# Interface.net
KiCad netlist of a schematic drawn in Altium Designer
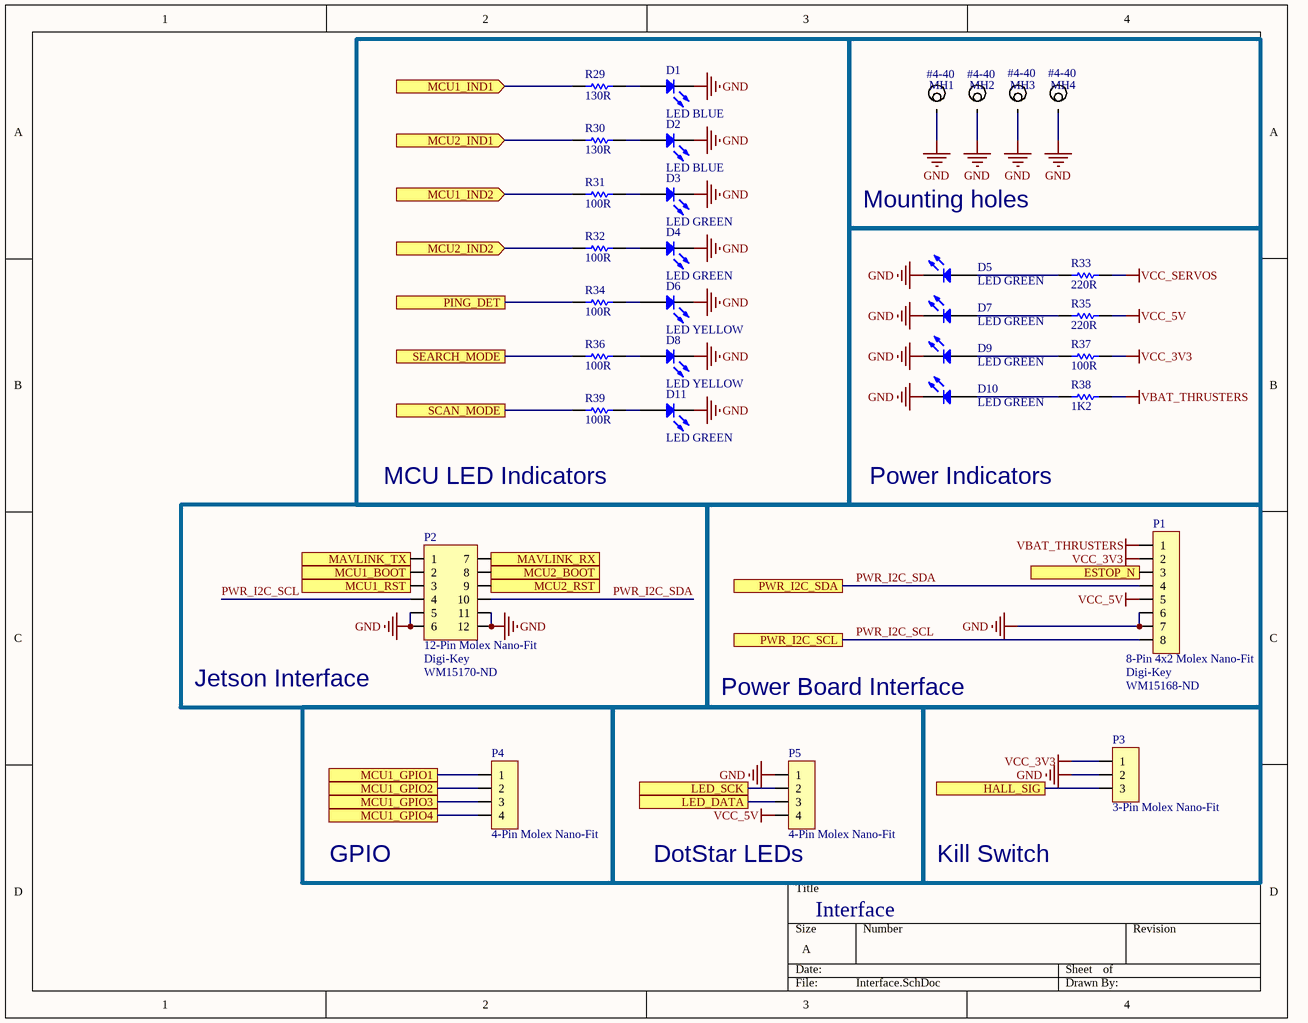
[diagram p0: Interface.SchDoc]

(export (version "E")
  (design (tool "Eeschema 10.0.6"))
  (components
    (comp (ref "D1")
      (value "LED BLUE")
      (footprint "LED_0805")
      (description "led")
      (libsource (lib "CMR_Miscellaneous_Devices") (part "LED0"))
    )
    (comp (ref "D2")
      (value "LED BLUE")
      (footprint "LED_0805")
      (description "led")
      (libsource (lib "CMR_Miscellaneous_Devices") (part "LED0"))
    )
    (comp (ref "D3")
      (value "LED GREEN")
      (footprint "LED_0805")
      (description "led")
      (fields
        (field (name "MANUFACTURER") "Lite-On Inc.")
        (field (name "MANUFACTURER PART NUMBER") "LTST-C171KGKT")
      )
      (libsource (lib "CMR_Miscellaneous_Devices") (part "LED0"))
    )
    (comp (ref "D4")
      (value "LED GREEN")
      (footprint "LED_0805")
      (description "led")
      (fields
        (field (name "MANUFACTURER") "Lite-On Inc.")
        (field (name "MANUFACTURER PART NUMBER") "LTST-C171KGKT")
      )
      (libsource (lib "CMR_Miscellaneous_Devices") (part "LED0"))
    )
    (comp (ref "D5")
      (value "LED GREEN")
      (footprint "LED_0805")
      (description "led")
      (fields
        (field (name "MANUFACTURER") "Lite-On Inc.")
        (field (name "MANUFACTURER PART NUMBER") "LTST-C171KGKT")
      )
      (libsource (lib "CMR_Miscellaneous_Devices") (part "LED0"))
    )
    (comp (ref "D6")
      (value "LED YELLOW")
      (footprint "LED_0805")
      (description "led\r\n LTST-C171KSKT")
      (fields
        (field (name "MANUFACTURER") "Lite-On Inc.")
        (field (name "MANUFACTURER PART NUMBER") "LTST-C171KGKT")
      )
      (libsource (lib "CMR_Miscellaneous_Devices") (part "LED0"))
    )
    (comp (ref "D7")
      (value "LED GREEN")
      (footprint "LED_0805")
      (description "led")
      (fields
        (field (name "MANUFACTURER") "Lite-On Inc.")
        (field (name "MANUFACTURER PART NUMBER") "LTST-C171KGKT")
      )
      (libsource (lib "CMR_Miscellaneous_Devices") (part "LED0"))
    )
    (comp (ref "D8")
      (value "LED YELLOW")
      (footprint "LED_0805")
      (description "led\r\n LTST-C171KSKT")
      (fields
        (field (name "MANUFACTURER") "Lite-On Inc.")
        (field (name "MANUFACTURER PART NUMBER") "LTST-C171KGKT")
      )
      (libsource (lib "CMR_Miscellaneous_Devices") (part "LED0"))
    )
    (comp (ref "D9")
      (value "LED GREEN")
      (footprint "LED_0805")
      (description "led")
      (fields
        (field (name "MANUFACTURER") "Lite-On Inc.")
        (field (name "MANUFACTURER PART NUMBER") "LTST-C171KGKT")
      )
      (libsource (lib "CMR_Miscellaneous_Devices") (part "LED0"))
    )
    (comp (ref "D10")
      (value "LED GREEN")
      (footprint "LED_0805")
      (description "led")
      (fields
        (field (name "MANUFACTURER") "Lite-On Inc.")
        (field (name "MANUFACTURER PART NUMBER") "LTST-C171KGKT")
      )
      (libsource (lib "CMR_Miscellaneous_Devices") (part "LED0"))
    )
    (comp (ref "D11")
      (value "LED GREEN")
      (footprint "LED_0805")
      (description "led")
      (fields
        (field (name "MANUFACTURER") "Lite-On Inc.")
        (field (name "MANUFACTURER PART NUMBER") "LTST-C171KGKT")
      )
      (libsource (lib "CMR_Miscellaneous_Devices") (part "LED0"))
    )
    (comp (ref "MH1")
      (value "#4-40")
      (footprint "Mounting Hole #4-40")
      (description "Mounting Hole for ANSI #4-40 w/ Flat Washer, Loose Fit")
      (libsource (lib "CMR_PCB_Components") (part "Mounting Hole #4-40, Loose Fit"))
    )
    (comp (ref "MH2")
      (value "#4-40")
      (footprint "Mounting Hole #4-40")
      (description "Mounting Hole for ANSI #4-40 w/ Flat Washer, Loose Fit")
      (libsource (lib "CMR_PCB_Components") (part "Mounting Hole #4-40, Loose Fit"))
    )
    (comp (ref "MH3")
      (value "#4-40")
      (footprint "Mounting Hole #4-40")
      (description "Mounting Hole for ANSI #4-40 w/ Flat Washer, Loose Fit")
      (libsource (lib "CMR_PCB_Components") (part "Mounting Hole #4-40, Loose Fit"))
    )
    (comp (ref "MH4")
      (value "#4-40")
      (footprint "Mounting Hole #4-40")
      (description "Mounting Hole for ANSI #4-40 w/ Flat Washer, Loose Fit")
      (libsource (lib "CMR_PCB_Components") (part "Mounting Hole #4-40, Loose Fit"))
    )
    (comp (ref "P1")
      (value "8-Pin 4x2 Molex Nano-Fit")
      (footprint "MOLEX NANO-FIT 2x4")
      (description "NanoFit RA Hdr TH DR 8Ckt")
      (fields
        (field (name "PART NUMBER") "105314-1216")
        (field (name "MANUFACTURER") "Molex")
        (field (name "SUPPLIER 1") "Digi-Key")
        (field (name "SUPPLIER PART NUMBER 1") "WM15168-ND")
      )
      (libsource (lib "CMR_Connectors") (part "8-Pin 2-Row Nano-Fit"))
    )
    (comp (ref "P2")
      (value "12-Pin Molex Nano-Fit")
      (footprint "MOLEX NANO-FIT 2X6 - Right Angle")
      (description "NanoFit RA Hdr TH DR 12Ckt")
      (fields (field (name "SUPPLIER 1") "Digi-Key") (field (name "SUPPLIER PART NUMBER 1") "WM15170-ND"))
      (libsource (lib "CMR_Connectors") (part "12-Pin 2-Row Nano-Fit"))
    )
    (comp (ref "P3")
      (value "3-Pin Molex Nano-Fit")
      (footprint "MOLEX NANO-FIT 1X3")
      (description "NanoFit RA Hdr TH SR 3Ckt")
      (fields (field (name "MANUFACTURER") "Molex") (field (name "PART NUMBER") "105313-1204"))
      (libsource (lib "CMR_Connectors") (part "3-Pin Nano-Fit"))
    )
    (comp (ref "P4")
      (value "4-Pin Molex Nano-Fit")
      (footprint "MOLEX NANO-FIT 1X4")
      (description "NanoFit RA Hdr TH SR 4Ckt")
      (fields (field (name "MANUFACTURER") "Molex") (field (name "PART NUMBER") "105313-1204"))
      (libsource (lib "CMR_Connectors") (part "4-Pin Nano-Fit"))
    )
    (comp (ref "P5")
      (value "4-Pin Molex Nano-Fit")
      (footprint "MOLEX NANO-FIT 1X4")
      (description "NanoFit RA Hdr TH SR 4Ckt")
      (fields (field (name "MANUFACTURER") "Molex") (field (name "PART NUMBER") "105313-1204"))
      (libsource (lib "CMR_Connectors") (part "4-Pin Nano-Fit"))
    )
    (comp (ref "R29")
      (value "130R")
      (footprint "RESC0603(1608)_N")
      (description "130R 0.1W 1% 0603 (1608 Metric)  SMD")
      (fields (field (name "POWER") "0.1 W") (field (name "TOLERANCE") "1 %"))
      (libsource (lib "Altium Content Vault") (part "CMP-1012-00409-1"))
    )
    (comp (ref "R30")
      (value "130R")
      (footprint "RESC0603(1608)_N")
      (description "130R 0.1W 1% 0603 (1608 Metric)  SMD")
      (fields (field (name "POWER") "0.1 W") (field (name "TOLERANCE") "1 %"))
      (libsource (lib "Altium Content Vault") (part "CMP-1012-00409-1"))
    )
    (comp (ref "R31")
      (value "100R")
      (footprint "RESC0603(1608)_N")
      (description "100R 0.1W 5% 0603 (1608 Metric)  SMD")
      (fields (field (name "TOLERANCE") "5 %") (field (name "POWER") "0.1 W"))
      (libsource (lib "Altium Content Vault") (part "CMP-1012-00050-1"))
    )
    (comp (ref "R32")
      (value "100R")
      (footprint "RESC0603(1608)_N")
      (description "100R 0.1W 5% 0603 (1608 Metric)  SMD")
      (fields (field (name "TOLERANCE") "5 %") (field (name "POWER") "0.1 W"))
      (libsource (lib "Altium Content Vault") (part "CMP-1012-00050-1"))
    )
    (comp (ref "R33")
      (value "220R")
      (footprint "RESC0603(1608)_N")
      (description "220R 0.1W 5% 0603 (1608 Metric)  SMD")
      (fields (field (name "POWER") "0.1 W") (field (name "TOLERANCE") "5 %"))
      (libsource (lib "Altium Content Vault") (part "RES"))
    )
    (comp (ref "R34")
      (value "100R")
      (footprint "RESC0603(1608)_N")
      (description "100R 0.1W 5% 0603 (1608 Metric)  SMD")
      (fields (field (name "TOLERANCE") "5 %") (field (name "POWER") "0.1 W"))
      (libsource (lib "Altium Content Vault") (part "CMP-1012-00050-1"))
    )
    (comp (ref "R35")
      (value "220R")
      (footprint "RESC0603(1608)_N")
      (description "220R 0.1W 5% 0603 (1608 Metric)  SMD")
      (fields (field (name "POWER") "0.1 W") (field (name "TOLERANCE") "5 %"))
      (libsource (lib "Altium Content Vault") (part "RES"))
    )
    (comp (ref "R36")
      (value "100R")
      (footprint "RESC0603(1608)_N")
      (description "100R 0.1W 5% 0603 (1608 Metric)  SMD")
      (fields (field (name "TOLERANCE") "5 %") (field (name "POWER") "0.1 W"))
      (libsource (lib "Altium Content Vault") (part "CMP-1012-00050-1"))
    )
    (comp (ref "R37")
      (value "100R")
      (footprint "RESC0603(1608)_N")
      (description "100R 0.1W 5% 0603 (1608 Metric)  SMD")
      (fields (field (name "TOLERANCE") "5 %") (field (name "POWER") "0.1 W"))
      (libsource (lib "Altium Content Vault") (part "RES"))
    )
    (comp (ref "R38")
      (value "1K2")
      (footprint "RESC0603(1608)_N")
      (description "1K2 0.1W 1% 0603 (1608 Metric)  SMD")
      (fields (field (name "POWER") "0.1 W") (field (name "TOLERANCE") "1 %"))
      (libsource (lib "Altium Content Vault") (part "RES"))
    )
    (comp (ref "R39")
      (value "100R")
      (footprint "RESC0603(1608)_N")
      (description "100R 0.1W 5% 0603 (1608 Metric)  SMD")
      (fields (field (name "TOLERANCE") "5 %") (field (name "POWER") "0.1 W"))
      (libsource (lib "Altium Content Vault") (part "CMP-1012-00050-1"))
    )
  )
  (nets
    (net (code "1") (name "/ESTOP_N") (class "Default")
      (node (ref "P1") (pin "3") (pinfunction "3_3") (pintype "passive"))
    )
    (net (code "2") (name "/HALL_SIG") (class "Default")
      (node (ref "P3") (pin "3") (pinfunction "3_3") (pintype "passive"))
    )
    (net (code "3") (name "/LED_DATA") (class "Default")
      (node (ref "P5") (pin "3") (pinfunction "3_3") (pintype "passive"))
    )
    (net (code "4") (name "/LED_SCK") (class "Default")
      (node (ref "P5") (pin "2") (pinfunction "2_2") (pintype "passive"))
    )
    (net (code "5") (name "/MAVLINK_RX") (class "Default")
      (node (ref "P2") (pin "7") (pinfunction "7_7") (pintype "passive"))
    )
    (net (code "6") (name "/MAVLINK_TX") (class "Default")
      (node (ref "P2") (pin "1") (pinfunction "1_1") (pintype "passive"))
    )
    (net (code "7") (name "/MCU1_BOOT") (class "Default")
      (node (ref "P2") (pin "2") (pinfunction "2_2") (pintype "passive"))
    )
    (net (code "8") (name "/MCU1_GPIO1") (class "Default")
      (node (ref "P4") (pin "1") (pinfunction "1_1") (pintype "passive"))
    )
    (net (code "9") (name "/MCU1_GPIO2") (class "Default")
      (node (ref "P4") (pin "2") (pinfunction "2_2") (pintype "passive"))
    )
    (net (code "10") (name "/MCU1_GPIO3") (class "Default")
      (node (ref "P4") (pin "3") (pinfunction "3_3") (pintype "passive"))
    )
    (net (code "11") (name "/MCU1_GPIO4") (class "Default")
      (node (ref "P4") (pin "4") (pinfunction "4_4") (pintype "passive"))
    )
    (net (code "12") (name "/MCU1_IND1") (class "Default")
      (node (ref "R29") (pin "1") (pinfunction "1_1") (pintype "passive"))
    )
    (net (code "13") (name "/MCU1_IND2") (class "Default")
      (node (ref "R31") (pin "1") (pinfunction "1_1") (pintype "passive"))
    )
    (net (code "14") (name "/MCU1_RST") (class "Default")
      (node (ref "P2") (pin "3") (pinfunction "3_3") (pintype "passive"))
    )
    (net (code "15") (name "/MCU2_BOOT") (class "Default")
      (node (ref "P2") (pin "8") (pinfunction "8_8") (pintype "passive"))
    )
    (net (code "16") (name "/MCU2_IND1") (class "Default")
      (node (ref "R30") (pin "1") (pinfunction "1_1") (pintype "passive"))
    )
    (net (code "17") (name "/MCU2_IND2") (class "Default")
      (node (ref "R32") (pin "1") (pinfunction "1_1") (pintype "passive"))
    )
    (net (code "18") (name "/MCU2_RST") (class "Default")
      (node (ref "P2") (pin "9") (pinfunction "9_9") (pintype "passive"))
    )
    (net (code "19") (name "/PING_DET") (class "Default")
      (node (ref "R34") (pin "1") (pinfunction "1_1") (pintype "passive"))
    )
    (net (code "20") (name "/PWR_I2C_SCL") (class "Default")
      (node (ref "P1") (pin "8") (pinfunction "8_8") (pintype "passive"))
      (node (ref "P2") (pin "4") (pinfunction "4_4") (pintype "passive"))
    )
    (net (code "21") (name "/PWR_I2C_SDA") (class "Default")
      (node (ref "P1") (pin "4") (pinfunction "4_4") (pintype "passive"))
      (node (ref "P2") (pin "10") (pinfunction "10_10") (pintype "passive"))
    )
    (net (code "22") (name "/SCAN_MODE") (class "Default")
      (node (ref "R39") (pin "1") (pinfunction "1_1") (pintype "passive"))
    )
    (net (code "23") (name "/SEARCH_MODE") (class "Default")
      (node (ref "R36") (pin "1") (pinfunction "1_1") (pintype "passive"))
    )
    (net (code "24") (name "GND") (class "Default")
      (node (ref "D1") (pin "1") (pinfunction "K_1") (pintype "passive"))
      (node (ref "D10") (pin "1") (pinfunction "K_1") (pintype "passive"))
      (node (ref "D11") (pin "1") (pinfunction "K_1") (pintype "passive"))
      (node (ref "D2") (pin "1") (pinfunction "K_1") (pintype "passive"))
      (node (ref "D3") (pin "1") (pinfunction "K_1") (pintype "passive"))
      (node (ref "D4") (pin "1") (pinfunction "K_1") (pintype "passive"))
      (node (ref "D5") (pin "1") (pinfunction "K_1") (pintype "passive"))
      (node (ref "D6") (pin "1") (pinfunction "K_1") (pintype "passive"))
      (node (ref "D7") (pin "1") (pinfunction "K_1") (pintype "passive"))
      (node (ref "D8") (pin "1") (pinfunction "K_1") (pintype "passive"))
      (node (ref "D9") (pin "1") (pinfunction "K_1") (pintype "passive"))
      (node (ref "MH1") (pin "0") (pinfunction "0_0") (pintype "passive"))
      (node (ref "MH2") (pin "0") (pinfunction "0_0") (pintype "passive"))
      (node (ref "MH3") (pin "0") (pinfunction "0_0") (pintype "passive"))
      (node (ref "MH4") (pin "0") (pinfunction "0_0") (pintype "passive"))
      (node (ref "P1") (pin "6") (pinfunction "6_6") (pintype "passive"))
      (node (ref "P1") (pin "7") (pinfunction "7_7") (pintype "passive"))
      (node (ref "P2") (pin "11") (pinfunction "11_11") (pintype "passive"))
      (node (ref "P2") (pin "12") (pinfunction "12_12") (pintype "passive"))
      (node (ref "P2") (pin "5") (pinfunction "5_5") (pintype "passive"))
      (node (ref "P2") (pin "6") (pinfunction "6_6") (pintype "passive"))
      (node (ref "P3") (pin "2") (pinfunction "2_2") (pintype "passive"))
      (node (ref "P5") (pin "1") (pinfunction "1_1") (pintype "passive"))
    )
    (net (code "25") (name "Net-(D1-A)") (class "Default")
      (node (ref "D1") (pin "2") (pinfunction "A_2") (pintype "passive"))
      (node (ref "R29") (pin "2") (pinfunction "2_2") (pintype "passive"))
    )
    (net (code "26") (name "Net-(D2-A)") (class "Default")
      (node (ref "D2") (pin "2") (pinfunction "A_2") (pintype "passive"))
      (node (ref "R30") (pin "2") (pinfunction "2_2") (pintype "passive"))
    )
    (net (code "27") (name "Net-(D3-A)") (class "Default")
      (node (ref "D3") (pin "2") (pinfunction "A_2") (pintype "passive"))
      (node (ref "R31") (pin "2") (pinfunction "2_2") (pintype "passive"))
    )
    (net (code "28") (name "Net-(D4-A)") (class "Default")
      (node (ref "D4") (pin "2") (pinfunction "A_2") (pintype "passive"))
      (node (ref "R32") (pin "2") (pinfunction "2_2") (pintype "passive"))
    )
    (net (code "29") (name "Net-(D5-A)") (class "Default")
      (node (ref "D5") (pin "2") (pinfunction "A_2") (pintype "passive"))
      (node (ref "R33") (pin "1") (pinfunction "1_1") (pintype "passive"))
    )
    (net (code "30") (name "Net-(D6-A)") (class "Default")
      (node (ref "D6") (pin "2") (pinfunction "A_2") (pintype "passive"))
      (node (ref "R34") (pin "2") (pinfunction "2_2") (pintype "passive"))
    )
    (net (code "31") (name "Net-(D7-A)") (class "Default")
      (node (ref "D7") (pin "2") (pinfunction "A_2") (pintype "passive"))
      (node (ref "R35") (pin "1") (pinfunction "1_1") (pintype "passive"))
    )
    (net (code "32") (name "Net-(D8-A)") (class "Default")
      (node (ref "D8") (pin "2") (pinfunction "A_2") (pintype "passive"))
      (node (ref "R36") (pin "2") (pinfunction "2_2") (pintype "passive"))
    )
    (net (code "33") (name "Net-(D9-A)") (class "Default")
      (node (ref "D9") (pin "2") (pinfunction "A_2") (pintype "passive"))
      (node (ref "R37") (pin "1") (pinfunction "1_1") (pintype "passive"))
    )
    (net (code "34") (name "Net-(D10-A)") (class "Default")
      (node (ref "D10") (pin "2") (pinfunction "A_2") (pintype "passive"))
      (node (ref "R38") (pin "1") (pinfunction "1_1") (pintype "passive"))
    )
    (net (code "35") (name "Net-(D11-A)") (class "Default")
      (node (ref "D11") (pin "2") (pinfunction "A_2") (pintype "passive"))
      (node (ref "R39") (pin "2") (pinfunction "2_2") (pintype "passive"))
    )
    (net (code "36") (name "VBAT_THRUSTERS") (class "Default")
      (node (ref "P1") (pin "1") (pinfunction "1_1") (pintype "passive"))
      (node (ref "R38") (pin "2") (pinfunction "2_2") (pintype "passive"))
    )
    (net (code "37") (name "VCC_3V3") (class "Default")
      (node (ref "P1") (pin "2") (pinfunction "2_2") (pintype "passive"))
      (node (ref "P3") (pin "1") (pinfunction "1_1") (pintype "passive"))
      (node (ref "R37") (pin "2") (pinfunction "2_2") (pintype "passive"))
    )
    (net (code "38") (name "VCC_5V") (class "Default")
      (node (ref "P1") (pin "5") (pinfunction "5_5") (pintype "passive"))
      (node (ref "P5") (pin "4") (pinfunction "4_4") (pintype "passive"))
      (node (ref "R35") (pin "2") (pinfunction "2_2") (pintype "passive"))
    )
    (net (code "39") (name "VCC_SERVOS") (class "Default")
      (node (ref "R33") (pin "2") (pinfunction "2_2") (pintype "passive"))
    )
  )
)
